# LED_Matrix_3_2_Power.net
KiCad netlist of a schematic drawn in EAGLE
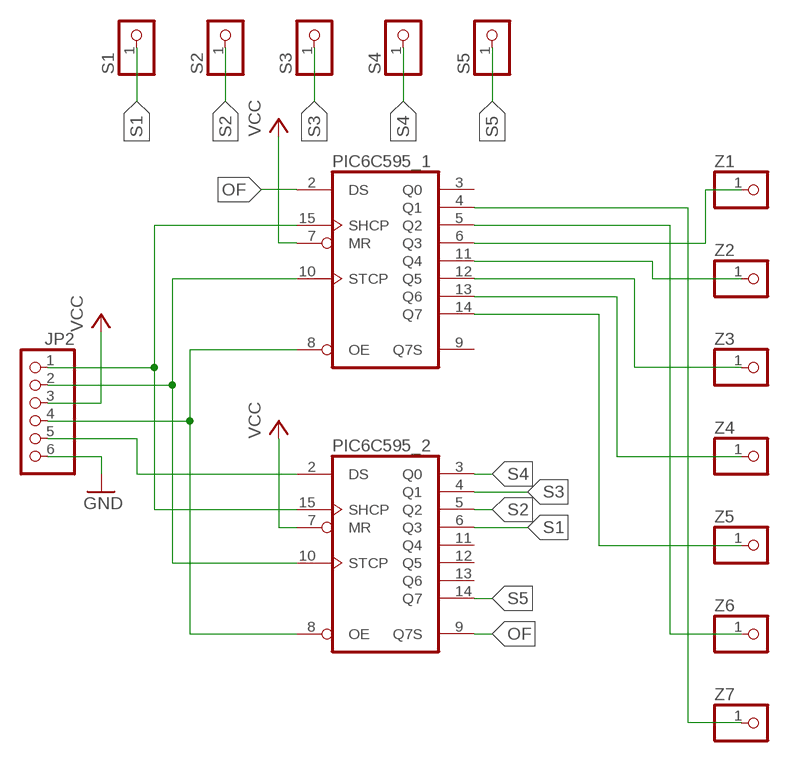
[diagram p0: schematic, sheet 1]

(export (version "E")
  (design (tool "Eeschema 10.0.6"))
  (components
    (comp (ref "JP2")
      (value "PINHD-1X6")
      (footprint "eagle-import:1X06")
      (libsource (lib "eagle-import") (part "PINHD-1X6"))
    )
    (comp (ref "PIC6C595_1")
      (value "PIC6C595D")
      (footprint "eagle-import:SO16")
      (libsource (lib "eagle-import") (part "PIC6C595D"))
    )
    (comp (ref "PIC6C595_2")
      (value "PIC6C595D")
      (footprint "eagle-import:SO16")
      (libsource (lib "eagle-import") (part "PIC6C595D"))
    )
    (comp (ref "S1")
      (value "PINHD-1X1")
      (footprint "eagle-import:1X01")
      (libsource (lib "eagle-import") (part "PINHD-1X1"))
    )
    (comp (ref "S2")
      (value "PINHD-1X1")
      (footprint "eagle-import:1X01")
      (libsource (lib "eagle-import") (part "PINHD-1X1"))
    )
    (comp (ref "S3")
      (value "PINHD-1X1")
      (footprint "eagle-import:1X01")
      (libsource (lib "eagle-import") (part "PINHD-1X1"))
    )
    (comp (ref "S4")
      (value "PINHD-1X1")
      (footprint "eagle-import:1X01")
      (libsource (lib "eagle-import") (part "PINHD-1X1"))
    )
    (comp (ref "S5")
      (value "PINHD-1X1")
      (footprint "eagle-import:1X01")
      (libsource (lib "eagle-import") (part "PINHD-1X1"))
    )
    (comp (ref "Z1")
      (value "PINHD-1X1")
      (footprint "eagle-import:1X01")
      (libsource (lib "eagle-import") (part "PINHD-1X1"))
    )
    (comp (ref "Z2")
      (value "PINHD-1X1")
      (footprint "eagle-import:1X01")
      (libsource (lib "eagle-import") (part "PINHD-1X1"))
    )
    (comp (ref "Z3")
      (value "PINHD-1X1")
      (footprint "eagle-import:1X01")
      (libsource (lib "eagle-import") (part "PINHD-1X1"))
    )
    (comp (ref "Z4")
      (value "PINHD-1X1")
      (footprint "eagle-import:1X01")
      (libsource (lib "eagle-import") (part "PINHD-1X1"))
    )
    (comp (ref "Z5")
      (value "PINHD-1X1")
      (footprint "eagle-import:1X01")
      (libsource (lib "eagle-import") (part "PINHD-1X1"))
    )
    (comp (ref "Z6")
      (value "PINHD-1X1")
      (footprint "eagle-import:1X01")
      (libsource (lib "eagle-import") (part "PINHD-1X1"))
    )
    (comp (ref "Z7")
      (value "PINHD-1X1")
      (footprint "eagle-import:1X01")
      (libsource (lib "eagle-import") (part "PINHD-1X1"))
    )
  )
  (nets
    (net (code "1") (name "GND") (class "Default")
      (node (ref "JP2") (pin "6") (pinfunction "6_6") (pintype "passive"))
    )
    (net (code "2") (name "Net-(PIC6C595_1A-OE)") (class "Default")
      (node (ref "JP2") (pin "4") (pinfunction "4_4") (pintype "passive"))
      (node (ref "PIC6C595_1") (pin "8") (pinfunction "OE_8") (pintype "input"))
      (node (ref "PIC6C595_2") (pin "8") (pinfunction "OE_8") (pintype "input"))
    )
    (net (code "3") (name "Net-(PIC6C595_1A-Q1)") (class "Default")
      (node (ref "PIC6C595_1") (pin "4") (pinfunction "Q1_4") (pintype "tri_state"))
      (node (ref "Z7") (pin "1") (pinfunction "1_1") (pintype "passive"))
    )
    (net (code "4") (name "Net-(PIC6C595_1A-Q2)") (class "Default")
      (node (ref "PIC6C595_1") (pin "5") (pinfunction "Q2_5") (pintype "tri_state"))
      (node (ref "Z6") (pin "1") (pinfunction "1_1") (pintype "passive"))
    )
    (net (code "5") (name "Net-(PIC6C595_1A-Q3)") (class "Default")
      (node (ref "PIC6C595_1") (pin "6") (pinfunction "Q3_6") (pintype "tri_state"))
      (node (ref "Z1") (pin "1") (pinfunction "1_1") (pintype "passive"))
    )
    (net (code "6") (name "Net-(PIC6C595_1A-Q4)") (class "Default")
      (node (ref "PIC6C595_1") (pin "11") (pinfunction "Q4_11") (pintype "tri_state"))
      (node (ref "Z2") (pin "1") (pinfunction "1_1") (pintype "passive"))
    )
    (net (code "7") (name "Net-(PIC6C595_1A-Q5)") (class "Default")
      (node (ref "PIC6C595_1") (pin "12") (pinfunction "Q5_12") (pintype "tri_state"))
      (node (ref "Z3") (pin "1") (pinfunction "1_1") (pintype "passive"))
    )
    (net (code "8") (name "Net-(PIC6C595_1A-Q6)") (class "Default")
      (node (ref "PIC6C595_1") (pin "13") (pinfunction "Q6_13") (pintype "tri_state"))
      (node (ref "Z4") (pin "1") (pinfunction "1_1") (pintype "passive"))
    )
    (net (code "9") (name "Net-(PIC6C595_1A-Q7)") (class "Default")
      (node (ref "PIC6C595_1") (pin "14") (pinfunction "Q7_14") (pintype "tri_state"))
      (node (ref "Z5") (pin "1") (pinfunction "1_1") (pintype "passive"))
    )
    (net (code "10") (name "Net-(PIC6C595_1A-SHCP)") (class "Default")
      (node (ref "JP2") (pin "1") (pinfunction "1_1") (pintype "passive"))
      (node (ref "PIC6C595_1") (pin "15") (pinfunction "SHCP_15") (pintype "input"))
      (node (ref "PIC6C595_2") (pin "15") (pinfunction "SHCP_15") (pintype "input"))
    )
    (net (code "11") (name "Net-(PIC6C595_1A-STCP)") (class "Default")
      (node (ref "JP2") (pin "2") (pinfunction "2_2") (pintype "passive"))
      (node (ref "PIC6C595_1") (pin "10") (pinfunction "STCP_10") (pintype "input"))
      (node (ref "PIC6C595_2") (pin "10") (pinfunction "STCP_10") (pintype "input"))
    )
    (net (code "12") (name "Net-(PIC6C595_2A-DS)") (class "Default")
      (node (ref "JP2") (pin "5") (pinfunction "5_5") (pintype "passive"))
      (node (ref "PIC6C595_2") (pin "2") (pinfunction "DS_2") (pintype "input"))
    )
    (net (code "13") (name "OF") (class "Default")
      (node (ref "PIC6C595_1") (pin "2") (pinfunction "DS_2") (pintype "input"))
      (node (ref "PIC6C595_2") (pin "9") (pinfunction "Q7S_9") (pintype "tri_state"))
    )
    (net (code "14") (name "S1") (class "Default")
      (node (ref "PIC6C595_2") (pin "6") (pinfunction "Q3_6") (pintype "tri_state"))
      (node (ref "S1") (pin "1") (pinfunction "1_1") (pintype "passive"))
    )
    (net (code "15") (name "S2") (class "Default")
      (node (ref "PIC6C595_2") (pin "5") (pinfunction "Q2_5") (pintype "tri_state"))
      (node (ref "S2") (pin "1") (pinfunction "1_1") (pintype "passive"))
    )
    (net (code "16") (name "S3") (class "Default")
      (node (ref "PIC6C595_2") (pin "4") (pinfunction "Q1_4") (pintype "tri_state"))
      (node (ref "S3") (pin "1") (pinfunction "1_1") (pintype "passive"))
    )
    (net (code "17") (name "S4") (class "Default")
      (node (ref "PIC6C595_2") (pin "3") (pinfunction "Q0_3") (pintype "tri_state"))
      (node (ref "S4") (pin "1") (pinfunction "1_1") (pintype "passive"))
    )
    (net (code "18") (name "S5") (class "Default")
      (node (ref "PIC6C595_2") (pin "14") (pinfunction "Q7_14") (pintype "tri_state"))
      (node (ref "S5") (pin "1") (pinfunction "1_1") (pintype "passive"))
    )
    (net (code "19") (name "VCC") (class "Default")
      (node (ref "JP2") (pin "3") (pinfunction "3_3") (pintype "passive"))
      (node (ref "PIC6C595_1") (pin "7") (pinfunction "MR_7") (pintype "input"))
      (node (ref "PIC6C595_2") (pin "7") (pinfunction "MR_7") (pintype "input"))
    )
    (net (code "20") (name "unconnected-(PIC6C595_1A-Q0-Pad3)") (class "Default")
      (node (ref "PIC6C595_1") (pin "3") (pinfunction "Q0_3") (pintype "tri_state"))
    )
    (net (code "21") (name "unconnected-(PIC6C595_1A-Q7S-Pad9)") (class "Default")
      (node (ref "PIC6C595_1") (pin "9") (pinfunction "Q7S_9") (pintype "tri_state"))
    )
    (net (code "22") (name "unconnected-(PIC6C595_2A-Q4-Pad11)") (class "Default")
      (node (ref "PIC6C595_2") (pin "11") (pinfunction "Q4_11") (pintype "tri_state"))
    )
    (net (code "23") (name "unconnected-(PIC6C595_2A-Q5-Pad12)") (class "Default")
      (node (ref "PIC6C595_2") (pin "12") (pinfunction "Q5_12") (pintype "tri_state"))
    )
    (net (code "24") (name "unconnected-(PIC6C595_2A-Q6-Pad13)") (class "Default")
      (node (ref "PIC6C595_2") (pin "13") (pinfunction "Q6_13") (pintype "tri_state"))
    )
  )
)
